# NodemcuShield_Light_Temp_LCD.net
KiCad netlist of a schematic drawn in Altium Designer
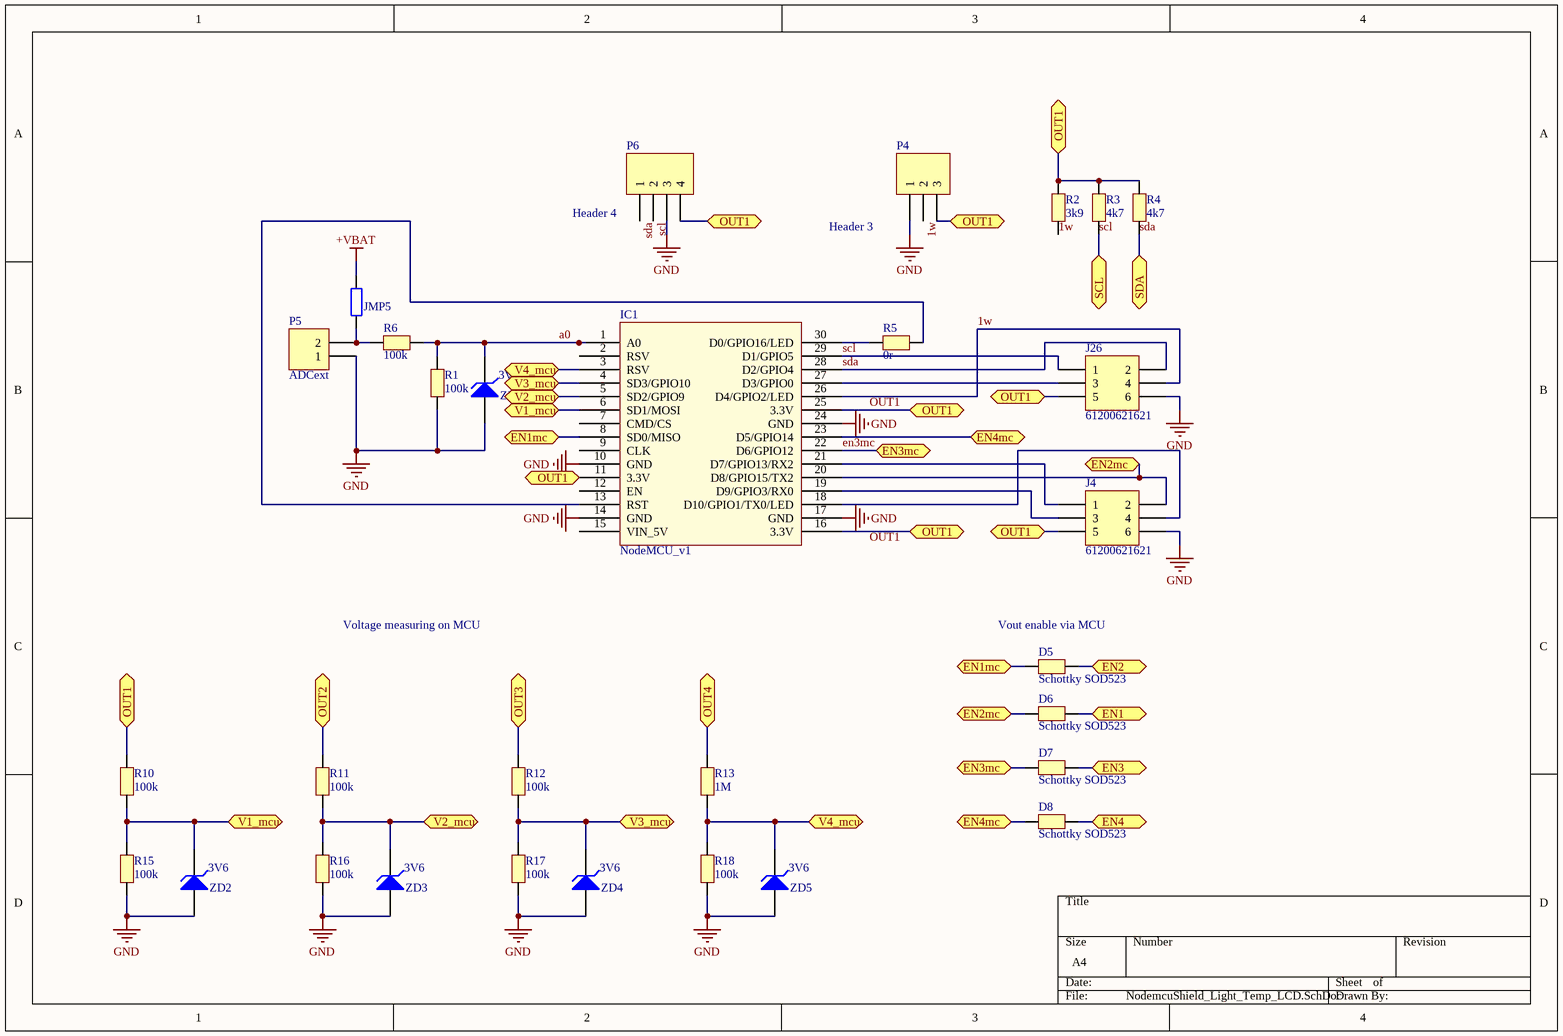
[diagram p0: NodemcuShield_Light_Temp_LCD.SchDoc]

(export (version "E")
  (design (tool "Eeschema 10.0.6"))
  (components
    (comp (ref "D5") (value "Schottky SOD523") (footprint "SOD523") (libsource (lib "") (part "Resistor_1")))
    (comp (ref "D6") (value "Schottky SOD523") (footprint "SOD523") (libsource (lib "") (part "Resistor_1")))
    (comp (ref "D7") (value "Schottky SOD523") (footprint "SOD523") (libsource (lib "") (part "Resistor_1")))
    (comp (ref "D8") (value "Schottky SOD523") (footprint "SOD523") (libsource (lib "") (part "Resistor_1")))
    (comp (ref "IC1")
      (value "NodeMCU_v1")
      (footprint "Nodemcu")
      (description "nodemcu")
      (libsource (lib "GeneralComponents") (part "NodeMCU_v1"))
    )
    (comp (ref "J4")
      (value "61200621621")
      (footprint "61200621621")
      (description "WR-BHD 2.54mm Male Box Header")
      (fields (field (name "MANUFACTURER") "Wurth Elektronik") (field (name "CREATED BY") "Baojun Chen"))
      (libsource (lib "ALTIUM-BHD_2_54_MALE_BOX_HEADER_6120XX21621-rev16b") (part "61200621621"))
    )
    (comp (ref "J26")
      (value "61200621621")
      (footprint "61200621621")
      (description "WR-BHD 2.54mm Male Box Header")
      (fields (field (name "MANUFACTURER") "Wurth Elektronik") (field (name "CREATED BY") "Baojun Chen"))
      (libsource (lib "ALTIUM-BHD_2_54_MALE_BOX_HEADER_6120XX21621-rev16b") (part "61200621621"))
    )
    (comp (ref "JMP5")
      (value "Resistor generic")
      (footprint "0603 RES")
      (description "Resistor SMD")
      (libsource (lib "IKSOR_LIB_main") (part "Resistor"))
    )
    (comp (ref "P4")
      (value "Header 3")
      (footprint "HDR1X3")
      (description "Header, 3-Pin")
      (fields (field (name "PUBLISHER") "Altium Limited"))
      (libsource (lib "Miscellaneous Connectors") (part "Header 3"))
    )
    (comp (ref "P5")
      (value "ADCext")
      (footprint "HDR1X2")
      (description "Header, 2-Pin")
      (fields (field (name "PUBLISHER") "Altium Limited"))
      (libsource (lib "Miscellaneous Connectors") (part "Header 2"))
    )
    (comp (ref "P6")
      (value "Header 4")
      (footprint "HDR1X4")
      (description "Header, 4-Pin")
      (fields (field (name "PUBLISHER") "Altium Limited"))
      (libsource (lib "Miscellaneous Connectors") (part "Header 4"))
    )
    (comp (ref "R1")
      (value "100k")
      (footprint "0603 RES")
      (description "Resistor 0603")
      (libsource (lib "GeneralComponents") (part "Resistor"))
    )
    (comp (ref "R2")
      (value "3k9")
      (footprint "0603 RES")
      (description "Resistor 0603")
      (libsource (lib "") (part "Resistor_2"))
    )
    (comp (ref "R3")
      (value "4k7")
      (footprint "0603 RES")
      (description "Resistor 0603")
      (libsource (lib "") (part "Resistor_2"))
    )
    (comp (ref "R4")
      (value "4k7")
      (footprint "0603 RES")
      (description "Resistor 0603")
      (libsource (lib "") (part "Resistor_2"))
    )
    (comp (ref "R5")
      (value "0r")
      (footprint "0603 RES")
      (description "Resistor 0603")
      (libsource (lib "") (part "Resistor_1"))
    )
    (comp (ref "R6")
      (value "100k")
      (footprint "0603 RES")
      (description "Resistor 0603")
      (libsource (lib "") (part "Resistor_1"))
    )
    (comp (ref "R10")
      (value "100k")
      (footprint "0603 RES")
      (description "Resistor 0805 smd")
      (libsource (lib "GeneralComponents") (part "Resistor"))
    )
    (comp (ref "R11")
      (value "100k")
      (footprint "0603 RES")
      (description "Resistor 0805 smd")
      (libsource (lib "GeneralComponents") (part "Resistor"))
    )
    (comp (ref "R12")
      (value "100k")
      (footprint "0603 RES")
      (description "Resistor 0805 smd")
      (libsource (lib "GeneralComponents") (part "Resistor"))
    )
    (comp (ref "R13")
      (value "1M")
      (footprint "0603 RES")
      (description "Resistor 0805 smd")
      (libsource (lib "GeneralComponents") (part "Resistor"))
    )
    (comp (ref "R15")
      (value "100k")
      (footprint "0603 RES")
      (description "Resistor 0805 smd")
      (libsource (lib "GeneralComponents") (part "Resistor"))
    )
    (comp (ref "R16")
      (value "100k")
      (footprint "0603 RES")
      (description "Resistor 0805 smd")
      (libsource (lib "GeneralComponents") (part "Resistor"))
    )
    (comp (ref "R17")
      (value "100k")
      (footprint "0603 RES")
      (description "Resistor 0805 smd")
      (libsource (lib "GeneralComponents") (part "Resistor"))
    )
    (comp (ref "R18")
      (value "100k")
      (footprint "0603 RES")
      (description "Resistor 0805 smd")
      (libsource (lib "GeneralComponents") (part "Resistor"))
    )
    (comp (ref "ZD1")
      (value "Diode Zener")
      (footprint "MELF_diode")
      (description "Zener")
      (fields (field (name "VALVE") "3V6"))
      (libsource (lib "IKSOR_LIB_main") (part "Diode Zener"))
    )
    (comp (ref "ZD2")
      (value "Diode Zener")
      (footprint "MELF_diode")
      (description "Zener")
      (fields (field (name "VALVE") "3V6"))
      (libsource (lib "IKSOR_LIB_main") (part "Diode Zener"))
    )
    (comp (ref "ZD3")
      (value "Diode Zener")
      (footprint "MELF_diode")
      (description "Zener")
      (fields (field (name "VALVE") "3V6"))
      (libsource (lib "IKSOR_LIB_main") (part "Diode Zener"))
    )
    (comp (ref "ZD4")
      (value "Diode Zener")
      (footprint "MELF_diode")
      (description "Zener")
      (fields (field (name "VALVE") "3V6"))
      (libsource (lib "IKSOR_LIB_main") (part "Diode Zener"))
    )
    (comp (ref "ZD5")
      (value "Diode Zener")
      (footprint "MELF_diode")
      (description "Zener")
      (fields (field (name "VALVE") "3V6"))
      (libsource (lib "IKSOR_LIB_main") (part "Diode Zener"))
    )
  )
  (nets
    (net (code "1") (name "+VBAT") (class "Default")
      (node (ref "JMP5") (pin "2") (pinfunction "2_2") (pintype "passive"))
    )
    (net (code "2") (name "/1w") (class "Default")
      (node (ref "IC1") (pin "26") (pinfunction "D4/GPIO2/LED_26") (pintype "passive"))
      (node (ref "J26") (pin "4") (pinfunction "4_4") (pintype "passive"))
      (node (ref "P4") (pin "2") (pinfunction "2_2") (pintype "passive"))
      (node (ref "R2") (pin "1") (pinfunction "1_1") (pintype "passive"))
    )
    (net (code "3") (name "/EN1") (class "Default")
      (node (ref "D6") (pin "1") (pinfunction "1_1") (pintype "passive"))
    )
    (net (code "4") (name "/EN1mc") (class "Default")
      (node (ref "D5") (pin "2") (pinfunction "2_2") (pintype "passive"))
      (node (ref "IC1") (pin "8") (pinfunction "SD0/MISO_8") (pintype "passive"))
    )
    (net (code "5") (name "/EN2") (class "Default")
      (node (ref "D5") (pin "1") (pinfunction "1_1") (pintype "passive"))
    )
    (net (code "6") (name "/EN2mc") (class "Default")
      (node (ref "D6") (pin "2") (pinfunction "2_2") (pintype "passive"))
      (node (ref "IC1") (pin "20") (pinfunction "D8/GPIO15/TX2_20") (pintype "passive"))
      (node (ref "J4") (pin "2") (pinfunction "2_2") (pintype "passive"))
    )
    (net (code "7") (name "/EN3") (class "Default")
      (node (ref "D7") (pin "1") (pinfunction "1_1") (pintype "passive"))
    )
    (net (code "8") (name "/EN4") (class "Default")
      (node (ref "D8") (pin "1") (pinfunction "1_1") (pintype "passive"))
    )
    (net (code "9") (name "/EN4mc") (class "Default")
      (node (ref "D8") (pin "2") (pinfunction "2_2") (pintype "passive"))
      (node (ref "IC1") (pin "23") (pinfunction "D5/GPIO14_23") (pintype "passive"))
    )
    (net (code "10") (name "/OUT1") (class "Default")
      (node (ref "IC1") (pin "11") (pinfunction "3.3V_11") (pintype "passive"))
      (node (ref "IC1") (pin "16") (pinfunction "3.3V_16") (pintype "passive"))
      (node (ref "IC1") (pin "25") (pinfunction "3.3V_25") (pintype "passive"))
      (node (ref "J26") (pin "5") (pinfunction "5_5") (pintype "passive"))
      (node (ref "J4") (pin "5") (pinfunction "5_5") (pintype "passive"))
      (node (ref "P4") (pin "3") (pinfunction "3_3") (pintype "passive"))
      (node (ref "P6") (pin "4") (pinfunction "4_4") (pintype "passive"))
      (node (ref "R10") (pin "1") (pinfunction "1_1") (pintype "passive"))
      (node (ref "R2") (pin "2") (pinfunction "2_2") (pintype "passive"))
      (node (ref "R3") (pin "2") (pinfunction "2_2") (pintype "passive"))
      (node (ref "R4") (pin "2") (pinfunction "2_2") (pintype "passive"))
    )
    (net (code "11") (name "/OUT2") (class "Default")
      (node (ref "R11") (pin "1") (pinfunction "1_1") (pintype "passive"))
    )
    (net (code "12") (name "/OUT3") (class "Default")
      (node (ref "R12") (pin "1") (pinfunction "1_1") (pintype "passive"))
    )
    (net (code "13") (name "/OUT4") (class "Default")
      (node (ref "R13") (pin "1") (pinfunction "1_1") (pintype "passive"))
    )
    (net (code "14") (name "/V1_mcu") (class "Default")
      (node (ref "IC1") (pin "6") (pinfunction "SD1/MOSI_6") (pintype "passive"))
      (node (ref "R10") (pin "2") (pinfunction "2_2") (pintype "passive"))
      (node (ref "R15") (pin "1") (pinfunction "1_1") (pintype "passive"))
      (node (ref "ZD2") (pin "2") (pinfunction "K_2") (pintype "passive"))
    )
    (net (code "15") (name "/V2_mcu") (class "Default")
      (node (ref "IC1") (pin "5") (pinfunction "SD2/GPIO9_5") (pintype "passive"))
      (node (ref "R11") (pin "2") (pinfunction "2_2") (pintype "passive"))
      (node (ref "R16") (pin "1") (pinfunction "1_1") (pintype "passive"))
      (node (ref "ZD3") (pin "2") (pinfunction "K_2") (pintype "passive"))
    )
    (net (code "16") (name "/V3_mcu") (class "Default")
      (node (ref "IC1") (pin "4") (pinfunction "SD3/GPIO10_4") (pintype "passive"))
      (node (ref "R12") (pin "2") (pinfunction "2_2") (pintype "passive"))
      (node (ref "R17") (pin "1") (pinfunction "1_1") (pintype "passive"))
      (node (ref "ZD4") (pin "2") (pinfunction "K_2") (pintype "passive"))
    )
    (net (code "17") (name "/V4_mcu") (class "Default")
      (node (ref "IC1") (pin "3") (pinfunction "RSV_3") (pintype "passive"))
      (node (ref "R13") (pin "2") (pinfunction "2_2") (pintype "passive"))
      (node (ref "R18") (pin "1") (pinfunction "1_1") (pintype "passive"))
      (node (ref "ZD5") (pin "2") (pinfunction "K_2") (pintype "passive"))
    )
    (net (code "18") (name "/a0") (class "Default")
      (node (ref "IC1") (pin "1") (pinfunction "A0_1") (pintype "passive"))
      (node (ref "R1") (pin "1") (pinfunction "1_1") (pintype "passive"))
      (node (ref "R6") (pin "1") (pinfunction "1_1") (pintype "passive"))
      (node (ref "ZD1") (pin "2") (pinfunction "K_2") (pintype "passive"))
    )
    (net (code "19") (name "/en3mc") (class "Default")
      (node (ref "D7") (pin "2") (pinfunction "2_2") (pintype "passive"))
      (node (ref "IC1") (pin "22") (pinfunction "D6/GPIO12_22") (pintype "passive"))
    )
    (net (code "20") (name "/scl") (class "Default")
      (node (ref "IC1") (pin "29") (pinfunction "D1/GPIO5_29") (pintype "passive"))
      (node (ref "J26") (pin "1") (pinfunction "1_1") (pintype "passive"))
      (node (ref "P6") (pin "2") (pinfunction "2_2") (pintype "passive"))
      (node (ref "R3") (pin "1") (pinfunction "1_1") (pintype "passive"))
    )
    (net (code "21") (name "/sda") (class "Default")
      (node (ref "IC1") (pin "28") (pinfunction "D2/GPIO4_28") (pintype "passive"))
      (node (ref "J26") (pin "2") (pinfunction "2_2") (pintype "passive"))
      (node (ref "P6") (pin "1") (pinfunction "1_1") (pintype "passive"))
      (node (ref "R4") (pin "1") (pinfunction "1_1") (pintype "passive"))
    )
    (net (code "22") (name "GND") (class "Default")
      (node (ref "IC1") (pin "10") (pinfunction "GND_10") (pintype "passive"))
      (node (ref "IC1") (pin "14") (pinfunction "GND_14") (pintype "passive"))
      (node (ref "IC1") (pin "17") (pinfunction "GND_17") (pintype "passive"))
      (node (ref "IC1") (pin "24") (pinfunction "GND_24") (pintype "passive"))
      (node (ref "J26") (pin "6") (pinfunction "6_6") (pintype "passive"))
      (node (ref "J4") (pin "6") (pinfunction "6_6") (pintype "passive"))
      (node (ref "P4") (pin "1") (pinfunction "1_1") (pintype "passive"))
      (node (ref "P5") (pin "1") (pinfunction "1_1") (pintype "passive"))
      (node (ref "P6") (pin "3") (pinfunction "3_3") (pintype "passive"))
      (node (ref "R1") (pin "2") (pinfunction "2_2") (pintype "passive"))
      (node (ref "R15") (pin "2") (pinfunction "2_2") (pintype "passive"))
      (node (ref "R16") (pin "2") (pinfunction "2_2") (pintype "passive"))
      (node (ref "R17") (pin "2") (pinfunction "2_2") (pintype "passive"))
      (node (ref "R18") (pin "2") (pinfunction "2_2") (pintype "passive"))
      (node (ref "ZD1") (pin "1") (pinfunction "A_1") (pintype "passive"))
      (node (ref "ZD2") (pin "1") (pinfunction "A_1") (pintype "passive"))
      (node (ref "ZD3") (pin "1") (pinfunction "A_1") (pintype "passive"))
      (node (ref "ZD4") (pin "1") (pinfunction "A_1") (pintype "passive"))
      (node (ref "ZD5") (pin "1") (pinfunction "A_1") (pintype "passive"))
    )
    (net (code "23") (name "Net-(IC1-D0{slash}GPIO16{slash}LED)") (class "Default")
      (node (ref "IC1") (pin "30") (pinfunction "D0/GPIO16/LED_30") (pintype "passive"))
      (node (ref "R5") (pin "2") (pinfunction "2_2") (pintype "passive"))
    )
    (net (code "24") (name "Net-(IC1-D3{slash}GPIO0)") (class "Default")
      (node (ref "IC1") (pin "27") (pinfunction "D3/GPIO0_27") (pintype "passive"))
      (node (ref "J26") (pin "3") (pinfunction "3_3") (pintype "passive"))
    )
    (net (code "25") (name "Net-(IC1-D7{slash}GPIO13{slash}RX2)") (class "Default")
      (node (ref "IC1") (pin "21") (pinfunction "D7/GPIO13/RX2_21") (pintype "passive"))
      (node (ref "J4") (pin "1") (pinfunction "1_1") (pintype "passive"))
    )
    (net (code "26") (name "Net-(IC1-D9{slash}GPIO3{slash}RX0)") (class "Default")
      (node (ref "IC1") (pin "19") (pinfunction "D9/GPIO3/RX0_19") (pintype "passive"))
      (node (ref "J4") (pin "3") (pinfunction "3_3") (pintype "passive"))
    )
    (net (code "27") (name "Net-(IC1-D10{slash}GPIO1{slash}TX0{slash}LED)") (class "Default")
      (node (ref "IC1") (pin "18") (pinfunction "D10/GPIO1/TX0/LED_18") (pintype "passive"))
      (node (ref "J4") (pin "4") (pinfunction "4_4") (pintype "passive"))
    )
    (net (code "28") (name "Net-(IC1-RST)") (class "Default")
      (node (ref "IC1") (pin "13") (pinfunction "RST_13") (pintype "passive"))
      (node (ref "R5") (pin "1") (pinfunction "1_1") (pintype "passive"))
    )
    (net (code "29") (name "Net-(JMP5-Pad1)") (class "Default")
      (node (ref "JMP5") (pin "1") (pinfunction "1_1") (pintype "passive"))
      (node (ref "P5") (pin "2") (pinfunction "2_2") (pintype "passive"))
      (node (ref "R6") (pin "2") (pinfunction "2_2") (pintype "passive"))
    )
    (net (code "30") (name "unconnected-(IC1-CLK-Pad9)") (class "Default")
      (node (ref "IC1") (pin "9") (pinfunction "CLK_9") (pintype "passive"))
    )
    (net (code "31") (name "unconnected-(IC1-CMD{slash}CS-Pad7)") (class "Default")
      (node (ref "IC1") (pin "7") (pinfunction "CMD/CS_7") (pintype "passive"))
    )
    (net (code "32") (name "unconnected-(IC1-EN-Pad12)") (class "Default")
      (node (ref "IC1") (pin "12") (pinfunction "EN_12") (pintype "passive"))
    )
    (net (code "33") (name "unconnected-(IC1-RSV-Pad2)") (class "Default")
      (node (ref "IC1") (pin "2") (pinfunction "RSV_2") (pintype "passive"))
    )
    (net (code "34") (name "unconnected-(IC1-VIN_5V-Pad15)") (class "Default")
      (node (ref "IC1") (pin "15") (pinfunction "VIN_5V_15") (pintype "passive"))
    )
  )
)
